# WheelBoard.net
KiCad netlist of a schematic drawn in Altium Designer
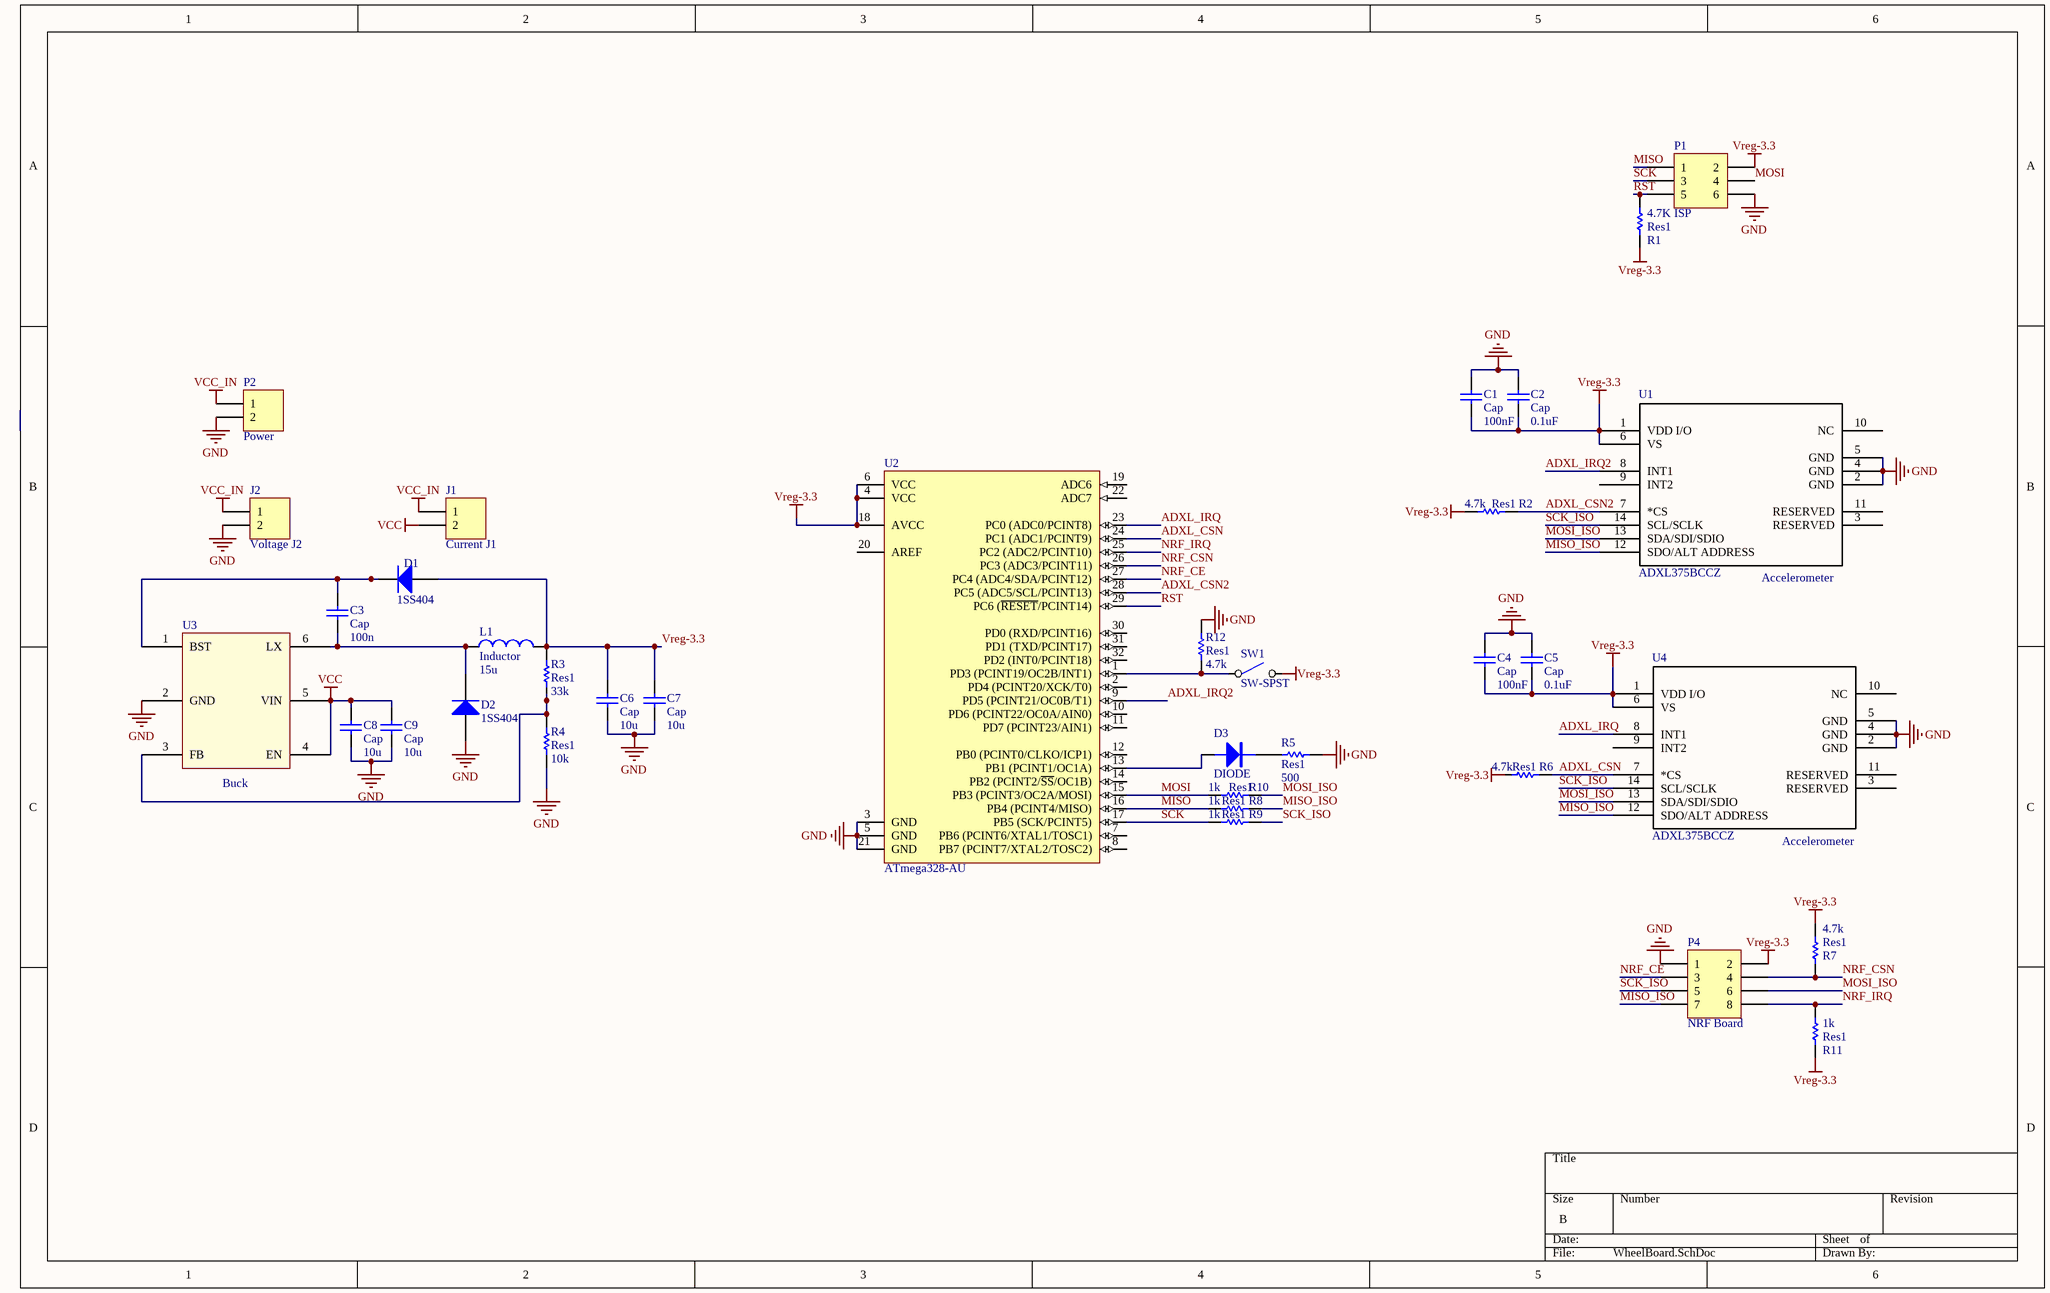
[diagram p0: WheelBoard.SchDoc]

(export (version "E")
  (design (tool "Eeschema 10.0.6"))
  (components
    (comp (ref "C1")
      (value "Cap")
      (footprint "0603E")
      (description "Capacitor")
      (fields (field (name "ALTIUM_VALUE") "100nF") (field (name "PUBLISHER") "Altium Limited"))
      (libsource (lib "Miscellaneous Devices") (part "Cap"))
    )
    (comp (ref "C2")
      (value "Cap")
      (footprint "0603E")
      (description "Capacitor")
      (fields (field (name "ALTIUM_VALUE") "0.1uF") (field (name "PUBLISHER") "Altium Limited"))
      (libsource (lib "Miscellaneous Devices") (part "Cap"))
    )
    (comp (ref "C3")
      (value "Cap")
      (footprint "0603E")
      (description "Capacitor")
      (fields (field (name "ALTIUM_VALUE") "100n") (field (name "PUBLISHER") "Altium Limited"))
      (libsource (lib "Miscellaneous Devices") (part "Cap"))
    )
    (comp (ref "C4")
      (value "Cap")
      (footprint "0603E")
      (description "Capacitor")
      (fields (field (name "ALTIUM_VALUE") "100nF") (field (name "PUBLISHER") "Altium Limited"))
      (libsource (lib "Miscellaneous Devices") (part "Cap"))
    )
    (comp (ref "C5")
      (value "Cap")
      (footprint "0603E")
      (description "Capacitor")
      (fields (field (name "ALTIUM_VALUE") "0.1uF") (field (name "PUBLISHER") "Altium Limited"))
      (libsource (lib "Miscellaneous Devices") (part "Cap"))
    )
    (comp (ref "C6")
      (value "Cap")
      (footprint "C0805")
      (description "Capacitor")
      (fields (field (name "ALTIUM_VALUE") "10u") (field (name "PUBLISHER") "Altium Limited"))
      (libsource (lib "Miscellaneous Devices") (part "Cap"))
    )
    (comp (ref "C7")
      (value "Cap")
      (footprint "C0805")
      (description "Capacitor")
      (fields (field (name "ALTIUM_VALUE") "10u") (field (name "PUBLISHER") "Altium Limited"))
      (libsource (lib "Miscellaneous Devices") (part "Cap"))
    )
    (comp (ref "C8")
      (value "Cap")
      (footprint "C0805")
      (description "Capacitor")
      (fields (field (name "ALTIUM_VALUE") "10u") (field (name "PUBLISHER") "Altium Limited"))
      (libsource (lib "Miscellaneous Devices") (part "Cap"))
    )
    (comp (ref "C9")
      (value "Cap")
      (footprint "C0805")
      (description "Capacitor")
      (fields (field (name "ALTIUM_VALUE") "10u") (field (name "PUBLISHER") "Altium Limited"))
      (libsource (lib "Miscellaneous Devices") (part "Cap"))
    )
    (comp (ref "D1")
      (value "1SS404")
      (footprint "SOD-323")
      (description "Silicon RF Switching Diode for VHF Band Switching in TV/VTR Tuners")
      (fields (field (name "PUBLISHER") "Altium Limited"))
      (libsource (lib "Infineon Discrete Diode") (part "BA592"))
    )
    (comp (ref "D2")
      (value "1SS404")
      (footprint "SOD-323")
      (description "Silicon RF Switching Diode for VHF Band Switching in TV/VTR Tuners")
      (fields (field (name "PUBLISHER") "Altium Limited"))
      (libsource (lib "Infineon Discrete Diode") (part "BA592"))
    )
    (comp (ref "D3")
      (value "DIODE")
      (footprint "D0805E")
      (description "Diode")
      (libsource (lib "KBsch01") (part "DIODE"))
    )
    (comp (ref "J1")
      (value "Current J1")
      (footprint "HDR1X2")
      (description "Header, 2-Pin")
      (fields (field (name "PUBLISHER") "Altium Limited"))
      (libsource (lib "Miscellaneous Connectors") (part "Header 2"))
    )
    (comp (ref "J2")
      (value "Voltage J2")
      (footprint "HDR1X2")
      (description "Header, 2-Pin")
      (fields (field (name "PUBLISHER") "Altium Limited"))
      (libsource (lib "Miscellaneous Connectors") (part "Header 2"))
    )
    (comp (ref "L1")
      (value "Inductor")
      (footprint "5828-INDUCTOR")
      (fields (field (name "ALTIUM_VALUE") "15u") (field (name "PUBLISHER") "Altium Limited"))
      (libsource (lib "Miscellaneous Devices") (part "Inductor"))
    )
    (comp (ref "P1")
      (value "ISP")
      (footprint "HDR2X3")
      (description "Header, 3-Pin, Dual row")
      (fields (field (name "PUBLISHER") "Altium Limited"))
      (libsource (lib "Miscellaneous Connectors") (part "Header 3X2"))
    )
    (comp (ref "P2")
      (value "Power")
      (footprint "HDR1X2")
      (description "Header, 2-Pin")
      (fields (field (name "PUBLISHER") "Altium Limited"))
      (libsource (lib "Miscellaneous Connectors") (part "Header 2"))
    )
    (comp (ref "P4")
      (value "NRF Board")
      (footprint "HDR2X4")
      (description "Header, 4-Pin, Dual row")
      (fields (field (name "PUBLISHER") "Altium Limited"))
      (libsource (lib "Miscellaneous Connectors") (part "Header 4X2"))
    )
    (comp (ref "R1")
      (value "Res1")
      (footprint "0603E")
      (description "Resistor")
      (fields (field (name "ALTIUM_VALUE") "4.7K") (field (name "PUBLISHER") "Altium Limited"))
      (libsource (lib "Miscellaneous Devices") (part "Res1"))
    )
    (comp (ref "R2")
      (value "Res1")
      (footprint "0603E")
      (description "Resistor")
      (fields (field (name "ALTIUM_VALUE") "4.7k") (field (name "PUBLISHER") "Altium Limited"))
      (libsource (lib "Miscellaneous Devices") (part "Res1"))
    )
    (comp (ref "R3")
      (value "Res1")
      (footprint "0603E")
      (description "Resistor")
      (fields (field (name "ALTIUM_VALUE") "33k") (field (name "PUBLISHER") "Altium Limited"))
      (libsource (lib "Miscellaneous Devices") (part "Res1"))
    )
    (comp (ref "R4")
      (value "Res1")
      (footprint "0603E")
      (description "Resistor")
      (fields (field (name "ALTIUM_VALUE") "10k") (field (name "PUBLISHER") "Altium Limited"))
      (libsource (lib "Miscellaneous Devices") (part "Res1"))
    )
    (comp (ref "R5")
      (value "Res1")
      (footprint "0603E")
      (description "Resistor")
      (fields (field (name "ALTIUM_VALUE") "500") (field (name "PUBLISHER") "Altium Limited"))
      (libsource (lib "Miscellaneous Devices") (part "Res1"))
    )
    (comp (ref "R6")
      (value "Res1")
      (footprint "0603E")
      (description "Resistor")
      (fields (field (name "ALTIUM_VALUE") "4.7k") (field (name "PUBLISHER") "Altium Limited"))
      (libsource (lib "Miscellaneous Devices") (part "Res1"))
    )
    (comp (ref "R7")
      (value "Res1")
      (footprint "0603E")
      (description "Resistor")
      (fields (field (name "ALTIUM_VALUE") "4.7k") (field (name "PUBLISHER") "Altium Limited"))
      (libsource (lib "Miscellaneous Devices") (part "Res1"))
    )
    (comp (ref "R8")
      (value "Res1")
      (footprint "0603E")
      (description "Resistor")
      (fields (field (name "ALTIUM_VALUE") "1k") (field (name "PUBLISHER") "Altium Limited"))
      (libsource (lib "Miscellaneous Devices") (part "Res1"))
    )
    (comp (ref "R9")
      (value "Res1")
      (footprint "0603E")
      (description "Resistor")
      (fields (field (name "ALTIUM_VALUE") "1k") (field (name "PUBLISHER") "Altium Limited"))
      (libsource (lib "Miscellaneous Devices") (part "Res1"))
    )
    (comp (ref "R10")
      (value "Res1")
      (footprint "0603E")
      (description "Resistor")
      (fields (field (name "ALTIUM_VALUE") "1k") (field (name "PUBLISHER") "Altium Limited"))
      (libsource (lib "Miscellaneous Devices") (part "Res1"))
    )
    (comp (ref "R11")
      (value "Res1")
      (footprint "0603E")
      (description "Resistor")
      (fields (field (name "ALTIUM_VALUE") "1k") (field (name "PUBLISHER") "Altium Limited"))
      (libsource (lib "Miscellaneous Devices") (part "Res1"))
    )
    (comp (ref "R12")
      (value "Res1")
      (footprint "0603E")
      (description "Resistor")
      (fields (field (name "ALTIUM_VALUE") "4.7k") (field (name "PUBLISHER") "Altium Limited"))
      (libsource (lib "Miscellaneous Devices") (part "Res1"))
    )
    (comp (ref "SW1")
      (value "SW-SPST")
      (footprint "Switch - SMD")
      (libsource (lib "KBsch01") (part "SW-SPST"))
    )
    (comp (ref "U1")
      (value "ADXL375BCCZ")
      (footprint "LGA_CC-14-1")
      (description "Imported")
      (libsource (lib "ADXL345") (part "ADXL345BCCZ"))
    )
    (comp (ref "U2")
      (value "ATmega328-AU")
      (footprint "32A_N")
      (fields (field (name "PUBLISHER") "Altium Limited"))
      (libsource (lib "Atmel Microcontroller 8-Bit megaAVR") (part "ATmega328-AU"))
    )
    (comp (ref "U3") (value "Buck") (footprint "SOT23-6") (libsource (lib "aoz1280ci") (part "Component_1")))
    (comp (ref "U4")
      (value "ADXL375BCCZ")
      (footprint "LGA_CC-14-1")
      (description "Imported")
      (libsource (lib "ADXL345") (part "ADXL345BCCZ"))
    )
  )
  (nets
    (net (code "1") (name "/ADXL_CSN") (class "Default")
      (node (ref "R6") (pin "2") (pinfunction "2_2") (pintype "passive"))
      (node (ref "U2") (pin "24") (pinfunction "PC1_(ADC1/PCINT9)_24") (pintype "bidirectional"))
      (node (ref "U4") (pin "7") (pinfunction "*CS_7") (pintype "passive"))
    )
    (net (code "2") (name "/ADXL_CSN2") (class "Default")
      (node (ref "R2") (pin "2") (pinfunction "2_2") (pintype "passive"))
      (node (ref "U1") (pin "7") (pinfunction "*CS_7") (pintype "passive"))
      (node (ref "U2") (pin "28") (pinfunction "PC5_(ADC5/SCL/PCINT13)_28") (pintype "bidirectional"))
    )
    (net (code "3") (name "/ADXL_IRQ") (class "Default")
      (node (ref "U2") (pin "23") (pinfunction "PC0_(ADC0/PCINT8)_23") (pintype "bidirectional"))
      (node (ref "U4") (pin "8") (pinfunction "INT1_8") (pintype "passive"))
    )
    (net (code "4") (name "/ADXL_IRQ2") (class "Default")
      (node (ref "U1") (pin "8") (pinfunction "INT1_8") (pintype "passive"))
      (node (ref "U2") (pin "9") (pinfunction "PD5_(PCINT21/OC0B/T1)_9") (pintype "bidirectional"))
    )
    (net (code "5") (name "/MISO") (class "Default")
      (node (ref "P1") (pin "1") (pinfunction "1_1") (pintype "passive"))
      (node (ref "R8") (pin "1") (pinfunction "1_1") (pintype "passive"))
      (node (ref "U2") (pin "16") (pinfunction "PB4_(PCINT4/MISO)_16") (pintype "bidirectional"))
    )
    (net (code "6") (name "/MISO_ISO") (class "Default")
      (node (ref "P4") (pin "7") (pinfunction "7_7") (pintype "passive"))
      (node (ref "R8") (pin "2") (pinfunction "2_2") (pintype "passive"))
      (node (ref "U1") (pin "12") (pinfunction "SDO/ALT_ADDRESS_12") (pintype "passive"))
      (node (ref "U4") (pin "12") (pinfunction "SDO/ALT_ADDRESS_12") (pintype "passive"))
    )
    (net (code "7") (name "/MOSI") (class "Default")
      (node (ref "P1") (pin "4") (pinfunction "4_4") (pintype "passive"))
      (node (ref "R10") (pin "2") (pinfunction "2_2") (pintype "passive"))
      (node (ref "U2") (pin "15") (pinfunction "PB3_(PCINT3/OC2A/MOSI)_15") (pintype "bidirectional"))
    )
    (net (code "8") (name "/MOSI_ISO") (class "Default")
      (node (ref "P4") (pin "6") (pinfunction "6_6") (pintype "passive"))
      (node (ref "R10") (pin "1") (pinfunction "1_1") (pintype "passive"))
      (node (ref "U1") (pin "13") (pinfunction "SDA/SDI/SDIO_13") (pintype "passive"))
      (node (ref "U4") (pin "13") (pinfunction "SDA/SDI/SDIO_13") (pintype "passive"))
    )
    (net (code "9") (name "/NRF_CE") (class "Default")
      (node (ref "P4") (pin "3") (pinfunction "3_3") (pintype "passive"))
      (node (ref "U2") (pin "27") (pinfunction "PC4_(ADC4/SDA/PCINT12)_27") (pintype "bidirectional"))
    )
    (net (code "10") (name "/NRF_CSN") (class "Default")
      (node (ref "P4") (pin "4") (pinfunction "4_4") (pintype "passive"))
      (node (ref "R7") (pin "1") (pinfunction "1_1") (pintype "passive"))
      (node (ref "U2") (pin "26") (pinfunction "PC3_(ADC3/PCINT11)_26") (pintype "bidirectional"))
    )
    (net (code "11") (name "/NRF_IRQ") (class "Default")
      (node (ref "P4") (pin "8") (pinfunction "8_8") (pintype "passive"))
      (node (ref "R11") (pin "1") (pinfunction "1_1") (pintype "passive"))
      (node (ref "U2") (pin "25") (pinfunction "PC2_(ADC2/PCINT10)_25") (pintype "bidirectional"))
    )
    (net (code "12") (name "/RST") (class "Default")
      (node (ref "P1") (pin "5") (pinfunction "5_5") (pintype "passive"))
      (node (ref "R1") (pin "1") (pinfunction "1_1") (pintype "passive"))
      (node (ref "U2") (pin "29") (pinfunction "PC6_(~{RESET}/PCINT14)_29") (pintype "bidirectional"))
    )
    (net (code "13") (name "/SCK") (class "Default")
      (node (ref "P1") (pin "3") (pinfunction "3_3") (pintype "passive"))
      (node (ref "R9") (pin "1") (pinfunction "1_1") (pintype "passive"))
      (node (ref "U2") (pin "17") (pinfunction "PB5_(SCK/PCINT5)_17") (pintype "bidirectional"))
    )
    (net (code "14") (name "/SCK_ISO") (class "Default")
      (node (ref "P4") (pin "5") (pinfunction "5_5") (pintype "passive"))
      (node (ref "R9") (pin "2") (pinfunction "2_2") (pintype "passive"))
      (node (ref "U1") (pin "14") (pinfunction "SCL/SCLK_14") (pintype "passive"))
      (node (ref "U4") (pin "14") (pinfunction "SCL/SCLK_14") (pintype "passive"))
    )
    (net (code "15") (name "GND") (class "Default")
      (node (ref "C1") (pin "2") (pinfunction "2_2") (pintype "passive"))
      (node (ref "C2") (pin "2") (pinfunction "2_2") (pintype "passive"))
      (node (ref "C4") (pin "2") (pinfunction "2_2") (pintype "passive"))
      (node (ref "C5") (pin "2") (pinfunction "2_2") (pintype "passive"))
      (node (ref "C6") (pin "1") (pinfunction "1_1") (pintype "passive"))
      (node (ref "C7") (pin "1") (pinfunction "1_1") (pintype "passive"))
      (node (ref "C8") (pin "2") (pinfunction "2_2") (pintype "passive"))
      (node (ref "C9") (pin "2") (pinfunction "2_2") (pintype "passive"))
      (node (ref "D2") (pin "2") (pinfunction "A_2") (pintype "passive"))
      (node (ref "J2") (pin "2") (pinfunction "2_2") (pintype "passive"))
      (node (ref "P1") (pin "6") (pinfunction "6_6") (pintype "passive"))
      (node (ref "P2") (pin "2") (pinfunction "2_2") (pintype "passive"))
      (node (ref "P4") (pin "1") (pinfunction "1_1") (pintype "passive"))
      (node (ref "R12") (pin "2") (pinfunction "2_2") (pintype "passive"))
      (node (ref "R4") (pin "1") (pinfunction "1_1") (pintype "passive"))
      (node (ref "R5") (pin "2") (pinfunction "2_2") (pintype "passive"))
      (node (ref "U1") (pin "2") (pinfunction "GND_2") (pintype "passive"))
      (node (ref "U1") (pin "4") (pinfunction "GND_4") (pintype "passive"))
      (node (ref "U1") (pin "5") (pinfunction "GND_5") (pintype "passive"))
      (node (ref "U2") (pin "21") (pinfunction "GND_21") (pintype "power_in"))
      (node (ref "U2") (pin "3") (pinfunction "GND_3") (pintype "power_in"))
      (node (ref "U2") (pin "5") (pinfunction "GND_5") (pintype "power_in"))
      (node (ref "U3") (pin "2") (pinfunction "GND_2") (pintype "passive"))
      (node (ref "U4") (pin "2") (pinfunction "GND_2") (pintype "passive"))
      (node (ref "U4") (pin "4") (pinfunction "GND_4") (pintype "passive"))
      (node (ref "U4") (pin "5") (pinfunction "GND_5") (pintype "passive"))
    )
    (net (code "16") (name "Net-(D1-K)") (class "Default")
      (node (ref "C3") (pin "1") (pinfunction "1_1") (pintype "passive"))
      (node (ref "D1") (pin "1") (pinfunction "K_1") (pintype "passive"))
      (node (ref "U3") (pin "1") (pinfunction "BST_1") (pintype "passive"))
    )
    (net (code "17") (name "Net-(D2-K)") (class "Default")
      (node (ref "C3") (pin "2") (pinfunction "2_2") (pintype "passive"))
      (node (ref "D2") (pin "1") (pinfunction "K_1") (pintype "passive"))
      (node (ref "L1") (pin "1") (pinfunction "1_1") (pintype "passive"))
      (node (ref "U3") (pin "6") (pinfunction "LX_6") (pintype "passive"))
    )
    (net (code "18") (name "Net-(D3-PadK)") (class "Default")
      (node (ref "D3") (pin "K") (pintype "passive"))
      (node (ref "R5") (pin "1") (pinfunction "1_1") (pintype "passive"))
    )
    (net (code "19") (name "Net-(U2-PB1_(PCINT1{slash}OC1A))") (class "Default")
      (node (ref "D3") (pin "A") (pintype "passive"))
      (node (ref "U2") (pin "13") (pinfunction "PB1_(PCINT1/OC1A)_13") (pintype "bidirectional"))
    )
    (net (code "20") (name "Net-(U2-PD3_(PCINT19{slash}OC2B{slash}INT1))") (class "Default")
      (node (ref "R12") (pin "1") (pinfunction "1_1") (pintype "passive"))
      (node (ref "SW1") (pin "1") (pintype "passive"))
      (node (ref "U2") (pin "1") (pinfunction "PD3_(PCINT19/OC2B/INT1)_1") (pintype "bidirectional"))
    )
    (net (code "21") (name "Net-(U3-FB)") (class "Default")
      (node (ref "R3") (pin "1") (pinfunction "1_1") (pintype "passive"))
      (node (ref "R4") (pin "2") (pinfunction "2_2") (pintype "passive"))
      (node (ref "U3") (pin "3") (pinfunction "FB_3") (pintype "passive"))
    )
    (net (code "22") (name "VCC") (class "Default")
      (node (ref "C8") (pin "1") (pinfunction "1_1") (pintype "passive"))
      (node (ref "C9") (pin "1") (pinfunction "1_1") (pintype "passive"))
      (node (ref "J1") (pin "2") (pinfunction "2_2") (pintype "passive"))
      (node (ref "U3") (pin "4") (pinfunction "EN_4") (pintype "passive"))
      (node (ref "U3") (pin "5") (pinfunction "VIN_5") (pintype "passive"))
    )
    (net (code "23") (name "VCC_IN") (class "Default")
      (node (ref "J1") (pin "1") (pinfunction "1_1") (pintype "passive"))
      (node (ref "J2") (pin "1") (pinfunction "1_1") (pintype "passive"))
      (node (ref "P2") (pin "1") (pinfunction "1_1") (pintype "passive"))
    )
    (net (code "24") (name "Vreg-3.3") (class "Default")
      (node (ref "C1") (pin "1") (pinfunction "1_1") (pintype "passive"))
      (node (ref "C2") (pin "1") (pinfunction "1_1") (pintype "passive"))
      (node (ref "C4") (pin "1") (pinfunction "1_1") (pintype "passive"))
      (node (ref "C5") (pin "1") (pinfunction "1_1") (pintype "passive"))
      (node (ref "C6") (pin "2") (pinfunction "2_2") (pintype "passive"))
      (node (ref "C7") (pin "2") (pinfunction "2_2") (pintype "passive"))
      (node (ref "D1") (pin "2") (pinfunction "A_2") (pintype "passive"))
      (node (ref "L1") (pin "2") (pinfunction "2_2") (pintype "passive"))
      (node (ref "P1") (pin "2") (pinfunction "2_2") (pintype "passive"))
      (node (ref "P4") (pin "2") (pinfunction "2_2") (pintype "passive"))
      (node (ref "R1") (pin "2") (pinfunction "2_2") (pintype "passive"))
      (node (ref "R11") (pin "2") (pinfunction "2_2") (pintype "passive"))
      (node (ref "R2") (pin "1") (pinfunction "1_1") (pintype "passive"))
      (node (ref "R3") (pin "2") (pinfunction "2_2") (pintype "passive"))
      (node (ref "R7") (pin "2") (pinfunction "2_2") (pintype "passive"))
      (node (ref "SW1") (pin "2") (pintype "passive"))
      (node (ref "U1") (pin "1") (pinfunction "VDD_I/O_1") (pintype "passive"))
      (node (ref "U1") (pin "6") (pinfunction "VS_6") (pintype "passive"))
      (node (ref "U2") (pin "18") (pinfunction "AVCC_18") (pintype "power_in"))
      (node (ref "U2") (pin "4") (pinfunction "VCC_4") (pintype "power_in"))
      (node (ref "U2") (pin "6") (pinfunction "VCC_6") (pintype "power_in"))
      (node (ref "U4") (pin "1") (pinfunction "VDD_I/O_1") (pintype "passive"))
      (node (ref "U4") (pin "6") (pinfunction "VS_6") (pintype "passive"))
    )
    (net (code "25") (name "unconnected-(R6-Pad1)") (class "Default")
      (node (ref "R6") (pin "1") (pinfunction "1_1") (pintype "passive"))
    )
    (net (code "26") (name "unconnected-(U1-INT2-Pad9)") (class "Default")
      (node (ref "U1") (pin "9") (pinfunction "INT2_9") (pintype "passive"))
    )
    (net (code "27") (name "unconnected-(U1-NC-Pad10)") (class "Default")
      (node (ref "U1") (pin "10") (pinfunction "NC_10") (pintype "passive"))
    )
    (net (code "28") (name "unconnected-(U1-RESERVED-Pad3)") (class "Default")
      (node (ref "U1") (pin "3") (pinfunction "RESERVED_3") (pintype "passive"))
    )
    (net (code "29") (name "unconnected-(U1-RESERVED-Pad11)") (class "Default")
      (node (ref "U1") (pin "11") (pinfunction "RESERVED_11") (pintype "passive"))
    )
    (net (code "30") (name "unconnected-(U2-ADC6-Pad19)") (class "Default")
      (node (ref "U2") (pin "19") (pinfunction "ADC6_19") (pintype "input"))
    )
    (net (code "31") (name "unconnected-(U2-ADC7-Pad22)") (class "Default")
      (node (ref "U2") (pin "22") (pinfunction "ADC7_22") (pintype "input"))
    )
    (net (code "32") (name "unconnected-(U2-AREF-Pad20)") (class "Default")
      (node (ref "U2") (pin "20") (pinfunction "AREF_20") (pintype "passive"))
    )
    (net (code "33") (name "unconnected-(U2-PB0_(PCINT0{slash}CLKO{slash}ICP1)-Pad12)") (class "Default")
      (node (ref "U2") (pin "12") (pinfunction "PB0_(PCINT0/CLKO/ICP1)_12") (pintype "bidirectional"))
    )
    (net (code "34") (name "unconnected-(U2-PB2_(PCINT2{slash}~{SS}{slash}OC1B)-Pad14)") (class "Default")
      (node (ref "U2") (pin "14") (pinfunction "PB2_(PCINT2/~{SS}/OC1B)_14") (pintype "bidirectional"))
    )
    (net (code "35") (name "unconnected-(U2-PB6_(PCINT6{slash}XTAL1{slash}TOSC1)-Pad7)") (class "Default")
      (node (ref "U2") (pin "7") (pinfunction "PB6_(PCINT6/XTAL1/TOSC1)_7") (pintype "bidirectional"))
    )
    (net (code "36") (name "unconnected-(U2-PB7_(PCINT7{slash}XTAL2{slash}TOSC2)-Pad8)") (class "Default")
      (node (ref "U2") (pin "8") (pinfunction "PB7_(PCINT7/XTAL2/TOSC2)_8") (pintype "bidirectional"))
    )
    (net (code "37") (name "unconnected-(U2-PD0_(RXD{slash}PCINT16)-Pad30)") (class "Default")
      (node (ref "U2") (pin "30") (pinfunction "PD0_(RXD/PCINT16)_30") (pintype "bidirectional"))
    )
    (net (code "38") (name "unconnected-(U2-PD1_(TXD{slash}PCINT17)-Pad31)") (class "Default")
      (node (ref "U2") (pin "31") (pinfunction "PD1_(TXD/PCINT17)_31") (pintype "bidirectional"))
    )
    (net (code "39") (name "unconnected-(U2-PD2_(INT0{slash}PCINT18)-Pad32)") (class "Default")
      (node (ref "U2") (pin "32") (pinfunction "PD2_(INT0/PCINT18)_32") (pintype "bidirectional"))
    )
    (net (code "40") (name "unconnected-(U2-PD4_(PCINT20{slash}XCK{slash}T0)-Pad2)") (class "Default")
      (node (ref "U2") (pin "2") (pinfunction "PD4_(PCINT20/XCK/T0)_2") (pintype "bidirectional"))
    )
    (net (code "41") (name "unconnected-(U2-PD6_(PCINT22{slash}OC0A{slash}AIN0)-Pad10)") (class "Default")
      (node (ref "U2") (pin "10") (pinfunction "PD6_(PCINT22/OC0A/AIN0)_10") (pintype "bidirectional"))
    )
    (net (code "42") (name "unconnected-(U2-PD7_(PCINT23{slash}AIN1)-Pad11)") (class "Default")
      (node (ref "U2") (pin "11") (pinfunction "PD7_(PCINT23/AIN1)_11") (pintype "bidirectional"))
    )
    (net (code "43") (name "unconnected-(U4-INT2-Pad9)") (class "Default")
      (node (ref "U4") (pin "9") (pinfunction "INT2_9") (pintype "passive"))
    )
    (net (code "44") (name "unconnected-(U4-NC-Pad10)") (class "Default")
      (node (ref "U4") (pin "10") (pinfunction "NC_10") (pintype "passive"))
    )
    (net (code "45") (name "unconnected-(U4-RESERVED-Pad3)") (class "Default")
      (node (ref "U4") (pin "3") (pinfunction "RESERVED_3") (pintype "passive"))
    )
    (net (code "46") (name "unconnected-(U4-RESERVED-Pad11)") (class "Default")
      (node (ref "U4") (pin "11") (pinfunction "RESERVED_11") (pintype "passive"))
    )
  )
)
